# TestShem.net
KiCad netlist of a schematic drawn in EAGLE
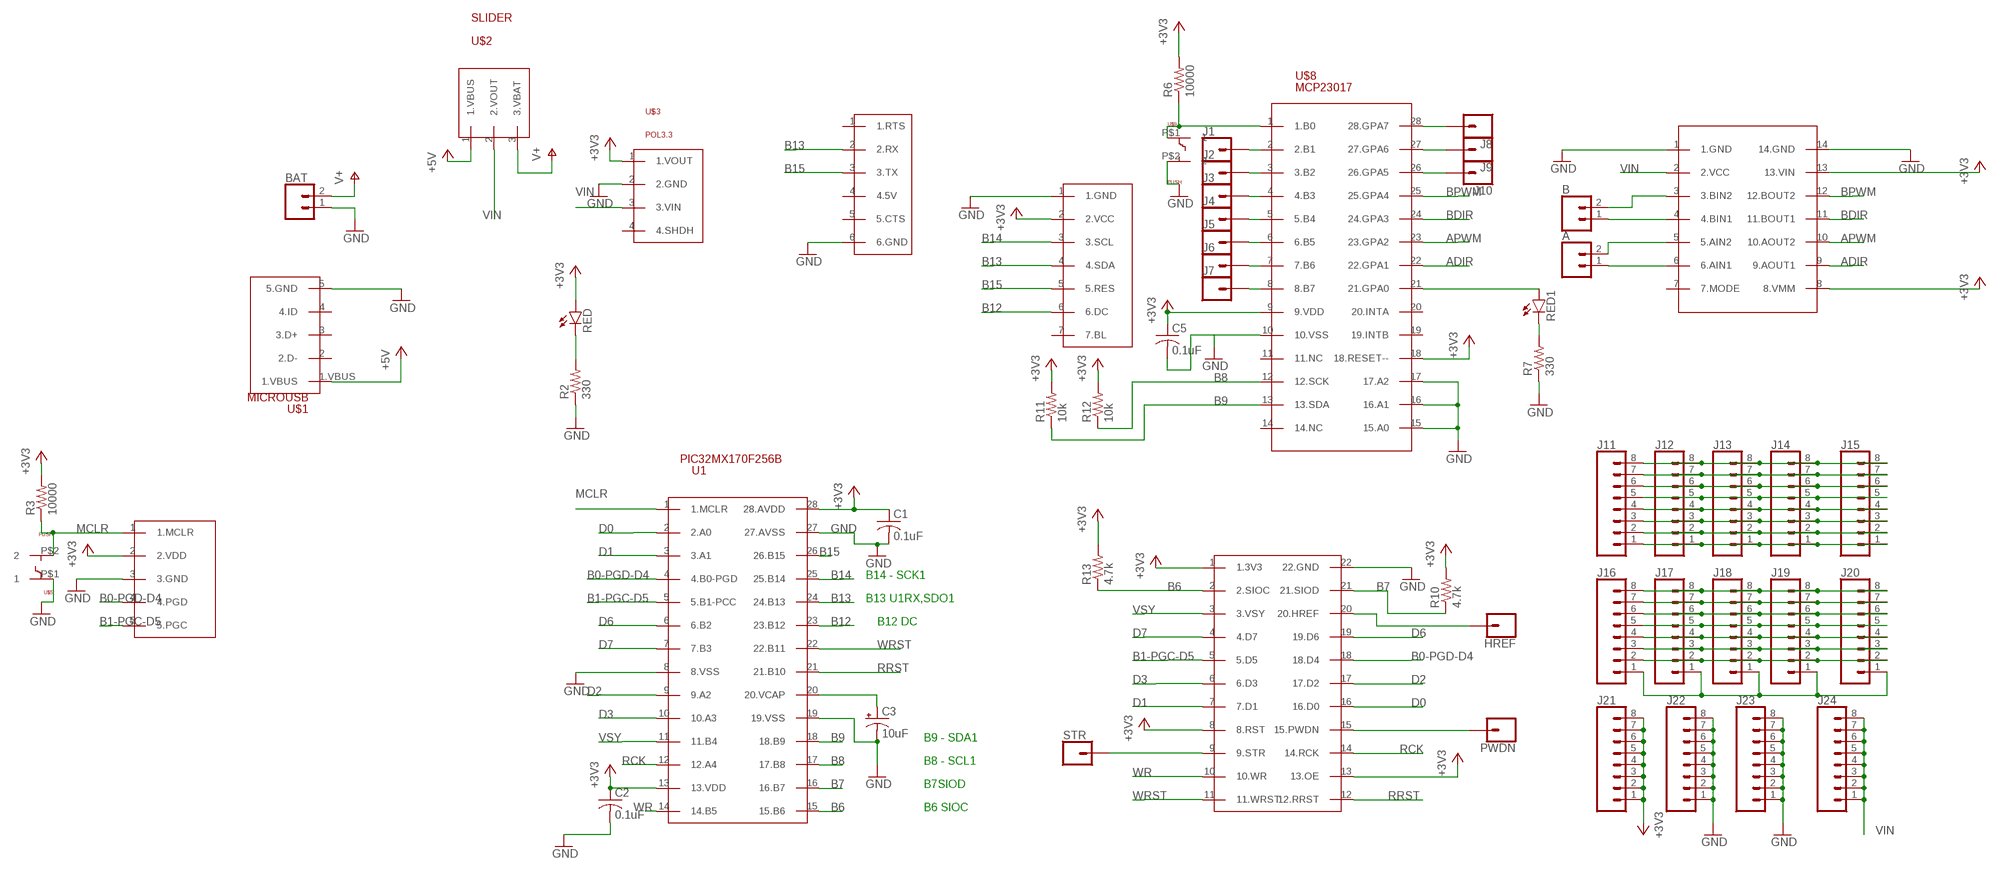
[diagram p0: schematic, sheet 1]

(export (version "E")
  (design (tool "Eeschema 10.0.6"))
  (components
    (comp (ref "A")
      (value "CONN_02")
      (footprint "eagle-import:1X02")
      (libsource (lib "eagle-import") (part "CONN_02"))
    )
    (comp (ref "B")
      (value "CONN_02")
      (footprint "eagle-import:1X02")
      (libsource (lib "eagle-import") (part "CONN_02"))
    )
    (comp (ref "BAT")
      (value "CONN_02")
      (footprint "eagle-import:1X02")
      (libsource (lib "eagle-import") (part "CONN_02"))
    )
    (comp (ref "C1")
      (value "0.1uF")
      (footprint "eagle-import:C025-030X050")
      (libsource (lib "eagle-import") (part "C-US025-030X050"))
    )
    (comp (ref "C2")
      (value "0.1uF")
      (footprint "eagle-import:C025-030X050")
      (libsource (lib "eagle-import") (part "C-US025-030X050"))
    )
    (comp (ref "C3")
      (value "10uF")
      (footprint "eagle-import:B45181B")
      (libsource (lib "eagle-import") (part "CPOL-USB45181B"))
    )
    (comp (ref "C5")
      (value "0.1uF")
      (footprint "eagle-import:C025-030X050")
      (libsource (lib "eagle-import") (part "C-US025-030X050"))
    )
    (comp (ref "HREF")
      (value "CONN_01")
      (footprint "eagle-import:1X01")
      (libsource (lib "eagle-import") (part "CONN_01"))
    )
    (comp (ref "J1")
      (value "CONN_01")
      (footprint "eagle-import:1X01")
      (libsource (lib "eagle-import") (part "CONN_01"))
    )
    (comp (ref "J2")
      (value "CONN_01")
      (footprint "eagle-import:1X01")
      (libsource (lib "eagle-import") (part "CONN_01"))
    )
    (comp (ref "J3")
      (value "CONN_01")
      (footprint "eagle-import:1X01")
      (libsource (lib "eagle-import") (part "CONN_01"))
    )
    (comp (ref "J4")
      (value "CONN_01")
      (footprint "eagle-import:1X01")
      (libsource (lib "eagle-import") (part "CONN_01"))
    )
    (comp (ref "J5")
      (value "CONN_01")
      (footprint "eagle-import:1X01")
      (libsource (lib "eagle-import") (part "CONN_01"))
    )
    (comp (ref "J6")
      (value "CONN_01")
      (footprint "eagle-import:1X01")
      (libsource (lib "eagle-import") (part "CONN_01"))
    )
    (comp (ref "J7")
      (value "CONN_01")
      (footprint "eagle-import:1X01")
      (libsource (lib "eagle-import") (part "CONN_01"))
    )
    (comp (ref "J8")
      (value "CONN_01")
      (footprint "eagle-import:1X01")
      (libsource (lib "eagle-import") (part "CONN_01"))
    )
    (comp (ref "J9")
      (value "CONN_01")
      (footprint "eagle-import:1X01")
      (libsource (lib "eagle-import") (part "CONN_01"))
    )
    (comp (ref "J10")
      (value "CONN_01")
      (footprint "eagle-import:1X01")
      (libsource (lib "eagle-import") (part "CONN_01"))
    )
    (comp (ref "J11")
      (value "CONN_08\"")
      (footprint "eagle-import:1X08")
      (libsource (lib "eagle-import") (part "CONN_08{dblquote}"))
    )
    (comp (ref "J12")
      (value "CONN_08\"")
      (footprint "eagle-import:1X08")
      (libsource (lib "eagle-import") (part "CONN_08{dblquote}"))
    )
    (comp (ref "J13")
      (value "CONN_08\"")
      (footprint "eagle-import:1X08")
      (libsource (lib "eagle-import") (part "CONN_08{dblquote}"))
    )
    (comp (ref "J14")
      (value "CONN_08\"")
      (footprint "eagle-import:1X08")
      (libsource (lib "eagle-import") (part "CONN_08{dblquote}"))
    )
    (comp (ref "J15")
      (value "CONN_08\"")
      (footprint "eagle-import:1X08")
      (libsource (lib "eagle-import") (part "CONN_08{dblquote}"))
    )
    (comp (ref "J16")
      (value "CONN_08\"")
      (footprint "eagle-import:1X08")
      (libsource (lib "eagle-import") (part "CONN_08{dblquote}"))
    )
    (comp (ref "J17")
      (value "CONN_08\"")
      (footprint "eagle-import:1X08")
      (libsource (lib "eagle-import") (part "CONN_08{dblquote}"))
    )
    (comp (ref "J18")
      (value "CONN_08\"")
      (footprint "eagle-import:1X08")
      (libsource (lib "eagle-import") (part "CONN_08{dblquote}"))
    )
    (comp (ref "J19")
      (value "CONN_08\"")
      (footprint "eagle-import:1X08")
      (libsource (lib "eagle-import") (part "CONN_08{dblquote}"))
    )
    (comp (ref "J20")
      (value "CONN_08\"")
      (footprint "eagle-import:1X08")
      (libsource (lib "eagle-import") (part "CONN_08{dblquote}"))
    )
    (comp (ref "J21")
      (value "CONN_08\"")
      (footprint "eagle-import:1X08")
      (libsource (lib "eagle-import") (part "CONN_08{dblquote}"))
    )
    (comp (ref "J22")
      (value "CONN_08\"")
      (footprint "eagle-import:1X08")
      (libsource (lib "eagle-import") (part "CONN_08{dblquote}"))
    )
    (comp (ref "J23")
      (value "CONN_08\"")
      (footprint "eagle-import:1X08")
      (libsource (lib "eagle-import") (part "CONN_08{dblquote}"))
    )
    (comp (ref "J24")
      (value "CONN_08\"")
      (footprint "eagle-import:1X08")
      (libsource (lib "eagle-import") (part "CONN_08{dblquote}"))
    )
    (comp (ref "PWDN")
      (value "CONN_01")
      (footprint "eagle-import:1X01")
      (libsource (lib "eagle-import") (part "CONN_01"))
    )
    (comp (ref "R2")
      (value "330")
      (footprint "eagle-import:0207_10")
      (libsource (lib "eagle-import") (part "R-US_0207/10"))
    )
    (comp (ref "R3")
      (value "10000")
      (footprint "eagle-import:0207_10")
      (libsource (lib "eagle-import") (part "R-US_0207/10"))
    )
    (comp (ref "R6")
      (value "10000")
      (footprint "eagle-import:0207_10")
      (libsource (lib "eagle-import") (part "R-US_0207/10"))
    )
    (comp (ref "R7")
      (value "330")
      (footprint "eagle-import:0207_10")
      (libsource (lib "eagle-import") (part "R-US_0207/10"))
    )
    (comp (ref "R10")
      (value "4.7k")
      (footprint "eagle-import:0207_10")
      (libsource (lib "eagle-import") (part "R-US_0207/10"))
    )
    (comp (ref "R11")
      (value "10k")
      (footprint "eagle-import:0207_10")
      (libsource (lib "eagle-import") (part "R-US_0207/10"))
    )
    (comp (ref "R12")
      (value "10k")
      (footprint "eagle-import:0207_10")
      (libsource (lib "eagle-import") (part "R-US_0207/10"))
    )
    (comp (ref "R13")
      (value "4.7k")
      (footprint "eagle-import:0207_10")
      (libsource (lib "eagle-import") (part "R-US_0207/10"))
    )
    (comp (ref "RED")
      (value "LED3MM")
      (footprint "eagle-import:LED3MM")
      (libsource (lib "eagle-import") (part "LED3MM"))
    )
    (comp (ref "RED1")
      (value "LED3MM")
      (footprint "eagle-import:LED3MM")
      (libsource (lib "eagle-import") (part "LED3MM"))
    )
    (comp (ref "STR")
      (value "CONN_01")
      (footprint "eagle-import:1X01")
      (libsource (lib "eagle-import") (part "CONN_01"))
    )
    (comp (ref "U$1")
      (value "MICROUSB")
      (footprint "eagle-import:MICROUSB")
      (libsource (lib "eagle-import") (part "MICROUSB"))
    )
    (comp (ref "U$2")
      (value "SLIDER")
      (footprint "eagle-import:SLIDER")
      (libsource (lib "eagle-import") (part "SLIDER"))
    )
    (comp (ref "U$3")
      (value "POL3.3")
      (footprint "eagle-import:POLOLU3.3")
      (libsource (lib "eagle-import") (part "POL3.3"))
    )
    (comp (ref "U$4")
      (value "SNAP")
      (footprint "eagle-import:1X05")
      (libsource (lib "eagle-import") (part "SNAP"))
    )
    (comp (ref "U$5")
      (value "PUSH")
      (footprint "eagle-import:PUSH")
      (libsource (lib "eagle-import") (part "PUSH"))
    )
    (comp (ref "U$6")
      (value "ADACP2104")
      (footprint "eagle-import:1X06V2")
      (libsource (lib "eagle-import") (part "ADACP2104"))
    )
    (comp (ref "U$7")
      (value "ST7789")
      (footprint "eagle-import:1X07")
      (libsource (lib "eagle-import") (part "ST7789"))
    )
    (comp (ref "U$8")
      (value "MCP23017")
      (footprint "eagle-import:DIL28-3")
      (libsource (lib "eagle-import") (part "MCP23017"))
    )
    (comp (ref "U$9")
      (value "PUSH")
      (footprint "eagle-import:PUSH")
      (libsource (lib "eagle-import") (part "PUSH"))
    )
    (comp (ref "U$10")
      (value "POLOLUDRV8835V2")
      (footprint "eagle-import:1X07V2")
      (libsource (lib "eagle-import") (part "POLOLUDRV8835V2"))
    )
    (comp (ref "U$11")
      (value "OV7670CAMFIXED")
      (footprint "eagle-import:1X02CAM")
      (libsource (lib "eagle-import") (part "OV7670CAMFIXED"))
    )
    (comp (ref "U1")
      (value "PIC32MX170F256B")
      (footprint "eagle-import:DIL28-3")
      (libsource (lib "eagle-import") (part "PIC32MX170F256B"))
    )
  )
  (nets
    (net (code "1") (name "+3V3") (class "Default")
      (node (ref "C1") (pin "1") (pinfunction "1_1") (pintype "passive"))
      (node (ref "C2") (pin "1") (pinfunction "1_1") (pintype "passive"))
      (node (ref "C5") (pin "1") (pinfunction "1_1") (pintype "passive"))
      (node (ref "J21") (pin "1") (pinfunction "1_1") (pintype "passive"))
      (node (ref "J21") (pin "2") (pinfunction "2_2") (pintype "passive"))
      (node (ref "J21") (pin "3") (pinfunction "3_3") (pintype "passive"))
      (node (ref "J21") (pin "4") (pinfunction "4_4") (pintype "passive"))
      (node (ref "J21") (pin "5") (pinfunction "5_5") (pintype "passive"))
      (node (ref "J21") (pin "6") (pinfunction "6_6") (pintype "passive"))
      (node (ref "J21") (pin "7") (pinfunction "7_7") (pintype "passive"))
      (node (ref "J21") (pin "8") (pinfunction "8_8") (pintype "passive"))
      (node (ref "R10") (pin "2") (pinfunction "2_2") (pintype "passive"))
      (node (ref "R11") (pin "2") (pinfunction "2_2") (pintype "passive"))
      (node (ref "R12") (pin "2") (pinfunction "2_2") (pintype "passive"))
      (node (ref "R13") (pin "2") (pinfunction "2_2") (pintype "passive"))
      (node (ref "R3") (pin "2") (pinfunction "2_2") (pintype "passive"))
      (node (ref "R6") (pin "2") (pinfunction "2_2") (pintype "passive"))
      (node (ref "RED") (pin "A") (pinfunction "A_A") (pintype "passive"))
      (node (ref "U$10") (pin "13") (pinfunction "13.VIN_13") (pintype "bidirectional"))
      (node (ref "U$10") (pin "8") (pinfunction "8.VMM_8") (pintype "bidirectional"))
      (node (ref "U$11") (pin "1") (pinfunction "1.3V3_1") (pintype "bidirectional"))
      (node (ref "U$11") (pin "13") (pinfunction "13.OE_13") (pintype "bidirectional"))
      (node (ref "U$11") (pin "8") (pinfunction "8.RST_8") (pintype "bidirectional"))
      (node (ref "U$3") (pin "1") (pinfunction "1.VOUT_1") (pintype "bidirectional"))
      (node (ref "U$4") (pin "2") (pinfunction "2.VDD_2") (pintype "bidirectional"))
      (node (ref "U$7") (pin "2") (pinfunction "2.VCC_2") (pintype "bidirectional"))
      (node (ref "U$8") (pin "18") (pinfunction "18.RESET--_18") (pintype "bidirectional"))
      (node (ref "U$8") (pin "9") (pinfunction "9.VDD_9") (pintype "bidirectional"))
      (node (ref "U1") (pin "13") (pinfunction "13.VDD_13") (pintype "bidirectional"))
      (node (ref "U1") (pin "28") (pinfunction "28.AVDD_28") (pintype "bidirectional"))
    )
    (net (code "2") (name "+5V") (class "Default")
      (node (ref "U$1") (pin "1.VBUS") (pinfunction "1.VBUS_1.VBUS") (pintype "bidirectional"))
      (node (ref "U$2") (pin "1") (pinfunction "1.VBUS_1") (pintype "bidirectional"))
    )
    (net (code "3") (name "/ADIR") (class "Default")
      (node (ref "U$10") (pin "9") (pinfunction "9.AOUT1_9") (pintype "bidirectional"))
      (node (ref "U$8") (pin "22") (pinfunction "22.GPA1_22") (pintype "bidirectional"))
    )
    (net (code "4") (name "/APWM") (class "Default")
      (node (ref "U$10") (pin "10") (pinfunction "10.AOUT2_10") (pintype "bidirectional"))
      (node (ref "U$8") (pin "23") (pinfunction "23.GPA2_23") (pintype "bidirectional"))
    )
    (net (code "5") (name "/B0-PGD-D4") (class "Default")
      (node (ref "U$11") (pin "18") (pinfunction "18.D4_18") (pintype "bidirectional"))
      (node (ref "U$4") (pin "4") (pinfunction "4.PGD_4") (pintype "bidirectional"))
      (node (ref "U1") (pin "4") (pinfunction "4.B0-PGD_4") (pintype "bidirectional"))
    )
    (net (code "6") (name "/B1-PGC-D5") (class "Default")
      (node (ref "U$11") (pin "5") (pinfunction "5.D5_5") (pintype "bidirectional"))
      (node (ref "U$4") (pin "5") (pinfunction "5.PGC_5") (pintype "bidirectional"))
      (node (ref "U1") (pin "5") (pinfunction "5.B1-PCC_5") (pintype "bidirectional"))
    )
    (net (code "7") (name "/B6") (class "Default")
      (node (ref "R13") (pin "1") (pinfunction "1_1") (pintype "passive"))
      (node (ref "U$11") (pin "2") (pinfunction "2.SIOC_2") (pintype "bidirectional"))
      (node (ref "U1") (pin "15") (pinfunction "15.B6_15") (pintype "bidirectional"))
    )
    (net (code "8") (name "/B7") (class "Default")
      (node (ref "R10") (pin "1") (pinfunction "1_1") (pintype "passive"))
      (node (ref "U$11") (pin "21") (pinfunction "21.SIOD_21") (pintype "bidirectional"))
      (node (ref "U1") (pin "16") (pinfunction "16.B7_16") (pintype "bidirectional"))
    )
    (net (code "9") (name "/B8") (class "Default")
      (node (ref "R12") (pin "1") (pinfunction "1_1") (pintype "passive"))
      (node (ref "U$8") (pin "12") (pinfunction "12.SCK_12") (pintype "bidirectional"))
      (node (ref "U1") (pin "17") (pinfunction "17.B8_17") (pintype "bidirectional"))
    )
    (net (code "10") (name "/B9") (class "Default")
      (node (ref "R11") (pin "1") (pinfunction "1_1") (pintype "passive"))
      (node (ref "U$8") (pin "13") (pinfunction "13.SDA_13") (pintype "bidirectional"))
      (node (ref "U1") (pin "18") (pinfunction "18.B9_18") (pintype "bidirectional"))
    )
    (net (code "11") (name "/B12") (class "Default")
      (node (ref "U$7") (pin "6") (pinfunction "6.DC_6") (pintype "bidirectional"))
      (node (ref "U1") (pin "23") (pinfunction "23.B12_23") (pintype "bidirectional"))
    )
    (net (code "12") (name "/B13") (class "Default")
      (node (ref "U$6") (pin "2") (pinfunction "2.RX_2") (pintype "bidirectional"))
      (node (ref "U$7") (pin "4") (pinfunction "4.SDA_4") (pintype "bidirectional"))
      (node (ref "U1") (pin "24") (pinfunction "24.B13_24") (pintype "bidirectional"))
    )
    (net (code "13") (name "/B14") (class "Default")
      (node (ref "U$7") (pin "3") (pinfunction "3.SCL_3") (pintype "bidirectional"))
      (node (ref "U1") (pin "25") (pinfunction "25.B14_25") (pintype "bidirectional"))
    )
    (net (code "14") (name "/B15") (class "Default")
      (node (ref "U$6") (pin "3") (pinfunction "3.TX_3") (pintype "bidirectional"))
      (node (ref "U$7") (pin "5") (pinfunction "5.RES_5") (pintype "bidirectional"))
      (node (ref "U1") (pin "26") (pinfunction "26.B15_26") (pintype "bidirectional"))
    )
    (net (code "15") (name "/BDIR") (class "Default")
      (node (ref "U$10") (pin "11") (pinfunction "11.BOUT1_11") (pintype "bidirectional"))
      (node (ref "U$8") (pin "24") (pinfunction "24.GPA3_24") (pintype "bidirectional"))
    )
    (net (code "16") (name "/BPWM") (class "Default")
      (node (ref "U$10") (pin "12") (pinfunction "12.BOUT2_12") (pintype "bidirectional"))
      (node (ref "U$8") (pin "25") (pinfunction "25.GPA4_25") (pintype "bidirectional"))
    )
    (net (code "17") (name "/D0") (class "Default")
      (node (ref "U$11") (pin "16") (pinfunction "16.D0_16") (pintype "bidirectional"))
      (node (ref "U1") (pin "2") (pinfunction "2.A0_2") (pintype "bidirectional"))
    )
    (net (code "18") (name "/D1") (class "Default")
      (node (ref "U$11") (pin "7") (pinfunction "7.D1_7") (pintype "bidirectional"))
      (node (ref "U1") (pin "3") (pinfunction "3.A1_3") (pintype "bidirectional"))
    )
    (net (code "19") (name "/D2") (class "Default")
      (node (ref "U$11") (pin "17") (pinfunction "17.D2_17") (pintype "bidirectional"))
      (node (ref "U1") (pin "9") (pinfunction "9.A2_9") (pintype "bidirectional"))
    )
    (net (code "20") (name "/D3") (class "Default")
      (node (ref "U$11") (pin "6") (pinfunction "6.D3_6") (pintype "bidirectional"))
      (node (ref "U1") (pin "10") (pinfunction "10.A3_10") (pintype "bidirectional"))
    )
    (net (code "21") (name "/D6") (class "Default")
      (node (ref "U$11") (pin "19") (pinfunction "19.D6_19") (pintype "bidirectional"))
      (node (ref "U1") (pin "6") (pinfunction "6.B2_6") (pintype "bidirectional"))
    )
    (net (code "22") (name "/D7") (class "Default")
      (node (ref "U$11") (pin "4") (pinfunction "4.D7_4") (pintype "bidirectional"))
      (node (ref "U1") (pin "7") (pinfunction "7.B3_7") (pintype "bidirectional"))
    )
    (net (code "23") (name "/MCLR") (class "Default")
      (node (ref "R3") (pin "1") (pinfunction "1_1") (pintype "passive"))
      (node (ref "U$4") (pin "1") (pinfunction "1.MCLR_1") (pintype "bidirectional"))
      (node (ref "U$5") (pin "P$2") (pinfunction "2_P$2") (pintype "bidirectional"))
      (node (ref "U1") (pin "1") (pinfunction "1.MCLR_1") (pintype "bidirectional"))
    )
    (net (code "24") (name "/RCK") (class "Default")
      (node (ref "U$11") (pin "14") (pinfunction "14.RCK_14") (pintype "bidirectional"))
      (node (ref "U1") (pin "12") (pinfunction "12.A4_12") (pintype "bidirectional"))
    )
    (net (code "25") (name "/RRST") (class "Default")
      (node (ref "U$11") (pin "12") (pinfunction "12.RRST_12") (pintype "bidirectional"))
      (node (ref "U1") (pin "21") (pinfunction "21.B10_21") (pintype "bidirectional"))
    )
    (net (code "26") (name "/VIN") (class "Default")
      (node (ref "J24") (pin "1") (pinfunction "1_1") (pintype "passive"))
      (node (ref "J24") (pin "2") (pinfunction "2_2") (pintype "passive"))
      (node (ref "J24") (pin "3") (pinfunction "3_3") (pintype "passive"))
      (node (ref "J24") (pin "4") (pinfunction "4_4") (pintype "passive"))
      (node (ref "J24") (pin "5") (pinfunction "5_5") (pintype "passive"))
      (node (ref "J24") (pin "6") (pinfunction "6_6") (pintype "passive"))
      (node (ref "J24") (pin "7") (pinfunction "7_7") (pintype "passive"))
      (node (ref "J24") (pin "8") (pinfunction "8_8") (pintype "passive"))
      (node (ref "U$10") (pin "2") (pinfunction "2.VCC_2") (pintype "bidirectional"))
      (node (ref "U$2") (pin "2") (pinfunction "2.VOUT_2") (pintype "bidirectional"))
      (node (ref "U$3") (pin "3") (pinfunction "3.VIN_3") (pintype "bidirectional"))
    )
    (net (code "27") (name "/VSY") (class "Default")
      (node (ref "U$11") (pin "3") (pinfunction "3.VSY_3") (pintype "bidirectional"))
      (node (ref "U1") (pin "11") (pinfunction "11.B4_11") (pintype "bidirectional"))
    )
    (net (code "28") (name "/WR") (class "Default")
      (node (ref "U$11") (pin "10") (pinfunction "10.WR_10") (pintype "bidirectional"))
      (node (ref "U1") (pin "14") (pinfunction "14.B5_14") (pintype "bidirectional"))
    )
    (net (code "29") (name "/WRST") (class "Default")
      (node (ref "U$11") (pin "11") (pinfunction "11.WRST_11") (pintype "bidirectional"))
      (node (ref "U1") (pin "22") (pinfunction "22.B11_22") (pintype "bidirectional"))
    )
    (net (code "30") (name "GND") (class "Default")
      (node (ref "BAT") (pin "1") (pinfunction "1_1") (pintype "passive"))
      (node (ref "C1") (pin "2") (pinfunction "2_2") (pintype "passive"))
      (node (ref "C2") (pin "2") (pinfunction "2_2") (pintype "passive"))
      (node (ref "C3") (pin "-") (pinfunction "-_-") (pintype "passive"))
      (node (ref "J22") (pin "1") (pinfunction "1_1") (pintype "passive"))
      (node (ref "J22") (pin "2") (pinfunction "2_2") (pintype "passive"))
      (node (ref "J22") (pin "3") (pinfunction "3_3") (pintype "passive"))
      (node (ref "J22") (pin "4") (pinfunction "4_4") (pintype "passive"))
      (node (ref "J22") (pin "5") (pinfunction "5_5") (pintype "passive"))
      (node (ref "J22") (pin "6") (pinfunction "6_6") (pintype "passive"))
      (node (ref "J22") (pin "7") (pinfunction "7_7") (pintype "passive"))
      (node (ref "J22") (pin "8") (pinfunction "8_8") (pintype "passive"))
      (node (ref "J23") (pin "1") (pinfunction "1_1") (pintype "passive"))
      (node (ref "J23") (pin "2") (pinfunction "2_2") (pintype "passive"))
      (node (ref "J23") (pin "3") (pinfunction "3_3") (pintype "passive"))
      (node (ref "J23") (pin "4") (pinfunction "4_4") (pintype "passive"))
      (node (ref "J23") (pin "5") (pinfunction "5_5") (pintype "passive"))
      (node (ref "J23") (pin "6") (pinfunction "6_6") (pintype "passive"))
      (node (ref "J23") (pin "7") (pinfunction "7_7") (pintype "passive"))
      (node (ref "J23") (pin "8") (pinfunction "8_8") (pintype "passive"))
      (node (ref "R2") (pin "1") (pinfunction "1_1") (pintype "passive"))
      (node (ref "R7") (pin "1") (pinfunction "1_1") (pintype "passive"))
      (node (ref "U$1") (pin "5") (pinfunction "5.GND_5") (pintype "bidirectional"))
      (node (ref "U$10") (pin "1") (pinfunction "1.GND_1") (pintype "bidirectional"))
      (node (ref "U$10") (pin "14") (pinfunction "14.GND_14") (pintype "bidirectional"))
      (node (ref "U$11") (pin "22") (pinfunction "22.GND_22") (pintype "bidirectional"))
      (node (ref "U$3") (pin "2") (pinfunction "2.GND_2") (pintype "bidirectional"))
      (node (ref "U$4") (pin "3") (pinfunction "3.GND_3") (pintype "bidirectional"))
      (node (ref "U$5") (pin "P$1") (pinfunction "1_P$1") (pintype "bidirectional"))
      (node (ref "U$6") (pin "6") (pinfunction "6.GND_6") (pintype "bidirectional"))
      (node (ref "U$7") (pin "1") (pinfunction "1.GND_1") (pintype "bidirectional"))
      (node (ref "U$8") (pin "15") (pinfunction "15.A0_15") (pintype "bidirectional"))
      (node (ref "U$8") (pin "16") (pinfunction "16.A1_16") (pintype "bidirectional"))
      (node (ref "U$8") (pin "17") (pinfunction "17.A2_17") (pintype "bidirectional"))
      (node (ref "U$9") (pin "P$2") (pinfunction "2_P$2") (pintype "bidirectional"))
      (node (ref "U1") (pin "19") (pinfunction "19.VSS_19") (pintype "bidirectional"))
      (node (ref "U1") (pin "27") (pinfunction "27.AVSS_27") (pintype "bidirectional"))
      (node (ref "U1") (pin "8") (pinfunction "8.VSS_8") (pintype "bidirectional"))
    )
    (net (code "31") (name "Net-(J11-Pad1)") (class "Default")
      (node (ref "J11") (pin "1") (pinfunction "1_1") (pintype "passive"))
      (node (ref "J12") (pin "1") (pinfunction "1_1") (pintype "passive"))
      (node (ref "J13") (pin "1") (pinfunction "1_1") (pintype "passive"))
      (node (ref "J14") (pin "1") (pinfunction "1_1") (pintype "passive"))
      (node (ref "J15") (pin "1") (pinfunction "1_1") (pintype "passive"))
    )
    (net (code "32") (name "Net-(J11-Pad2)") (class "Default")
      (node (ref "J11") (pin "2") (pinfunction "2_2") (pintype "passive"))
      (node (ref "J12") (pin "2") (pinfunction "2_2") (pintype "passive"))
      (node (ref "J13") (pin "2") (pinfunction "2_2") (pintype "passive"))
      (node (ref "J14") (pin "2") (pinfunction "2_2") (pintype "passive"))
      (node (ref "J15") (pin "2") (pinfunction "2_2") (pintype "passive"))
    )
    (net (code "33") (name "Net-(J11-Pad3)") (class "Default")
      (node (ref "J11") (pin "3") (pinfunction "3_3") (pintype "passive"))
      (node (ref "J12") (pin "3") (pinfunction "3_3") (pintype "passive"))
      (node (ref "J13") (pin "3") (pinfunction "3_3") (pintype "passive"))
      (node (ref "J14") (pin "3") (pinfunction "3_3") (pintype "passive"))
      (node (ref "J15") (pin "3") (pinfunction "3_3") (pintype "passive"))
    )
    (net (code "34") (name "Net-(J11-Pad4)") (class "Default")
      (node (ref "J11") (pin "4") (pinfunction "4_4") (pintype "passive"))
      (node (ref "J12") (pin "4") (pinfunction "4_4") (pintype "passive"))
      (node (ref "J13") (pin "4") (pinfunction "4_4") (pintype "passive"))
      (node (ref "J14") (pin "4") (pinfunction "4_4") (pintype "passive"))
      (node (ref "J15") (pin "4") (pinfunction "4_4") (pintype "passive"))
    )
    (net (code "35") (name "Net-(J11-Pad5)") (class "Default")
      (node (ref "J11") (pin "5") (pinfunction "5_5") (pintype "passive"))
      (node (ref "J12") (pin "5") (pinfunction "5_5") (pintype "passive"))
      (node (ref "J13") (pin "5") (pinfunction "5_5") (pintype "passive"))
      (node (ref "J14") (pin "5") (pinfunction "5_5") (pintype "passive"))
      (node (ref "J15") (pin "5") (pinfunction "5_5") (pintype "passive"))
    )
    (net (code "36") (name "Net-(J11-Pad6)") (class "Default")
      (node (ref "J11") (pin "6") (pinfunction "6_6") (pintype "passive"))
      (node (ref "J12") (pin "6") (pinfunction "6_6") (pintype "passive"))
      (node (ref "J13") (pin "6") (pinfunction "6_6") (pintype "passive"))
      (node (ref "J14") (pin "6") (pinfunction "6_6") (pintype "passive"))
      (node (ref "J15") (pin "6") (pinfunction "6_6") (pintype "passive"))
    )
    (net (code "37") (name "Net-(J11-Pad7)") (class "Default")
      (node (ref "J11") (pin "7") (pinfunction "7_7") (pintype "passive"))
      (node (ref "J12") (pin "7") (pinfunction "7_7") (pintype "passive"))
      (node (ref "J13") (pin "7") (pinfunction "7_7") (pintype "passive"))
      (node (ref "J14") (pin "7") (pinfunction "7_7") (pintype "passive"))
      (node (ref "J15") (pin "7") (pinfunction "7_7") (pintype "passive"))
    )
    (net (code "38") (name "Net-(J11-Pad8)") (class "Default")
      (node (ref "J11") (pin "8") (pinfunction "8_8") (pintype "passive"))
      (node (ref "J12") (pin "8") (pinfunction "8_8") (pintype "passive"))
      (node (ref "J13") (pin "8") (pinfunction "8_8") (pintype "passive"))
      (node (ref "J14") (pin "8") (pinfunction "8_8") (pintype "passive"))
      (node (ref "J15") (pin "8") (pinfunction "8_8") (pintype "passive"))
    )
    (net (code "39") (name "Net-(J16-Pad1)") (class "Default")
      (node (ref "J16") (pin "1") (pinfunction "1_1") (pintype "passive"))
      (node (ref "J17") (pin "1") (pinfunction "1_1") (pintype "passive"))
      (node (ref "J18") (pin "1") (pinfunction "1_1") (pintype "passive"))
      (node (ref "J19") (pin "1") (pinfunction "1_1") (pintype "passive"))
      (node (ref "J20") (pin "1") (pinfunction "1_1") (pintype "passive"))
    )
    (net (code "40") (name "Net-(J16-Pad2)") (class "Default")
      (node (ref "J16") (pin "2") (pinfunction "2_2") (pintype "passive"))
      (node (ref "J17") (pin "2") (pinfunction "2_2") (pintype "passive"))
      (node (ref "J18") (pin "2") (pinfunction "2_2") (pintype "passive"))
      (node (ref "J19") (pin "2") (pinfunction "2_2") (pintype "passive"))
      (node (ref "J20") (pin "2") (pinfunction "2_2") (pintype "passive"))
    )
    (net (code "41") (name "Net-(J16-Pad3)") (class "Default")
      (node (ref "J16") (pin "3") (pinfunction "3_3") (pintype "passive"))
      (node (ref "J17") (pin "3") (pinfunction "3_3") (pintype "passive"))
      (node (ref "J18") (pin "3") (pinfunction "3_3") (pintype "passive"))
      (node (ref "J19") (pin "3") (pinfunction "3_3") (pintype "passive"))
      (node (ref "J20") (pin "3") (pinfunction "3_3") (pintype "passive"))
    )
    (net (code "42") (name "Net-(J16-Pad4)") (class "Default")
      (node (ref "J16") (pin "4") (pinfunction "4_4") (pintype "passive"))
      (node (ref "J17") (pin "4") (pinfunction "4_4") (pintype "passive"))
      (node (ref "J18") (pin "4") (pinfunction "4_4") (pintype "passive"))
      (node (ref "J19") (pin "4") (pinfunction "4_4") (pintype "passive"))
      (node (ref "J20") (pin "4") (pinfunction "4_4") (pintype "passive"))
    )
    (net (code "43") (name "Net-(J16-Pad5)") (class "Default")
      (node (ref "J16") (pin "5") (pinfunction "5_5") (pintype "passive"))
      (node (ref "J17") (pin "5") (pinfunction "5_5") (pintype "passive"))
      (node (ref "J18") (pin "5") (pinfunction "5_5") (pintype "passive"))
      (node (ref "J19") (pin "5") (pinfunction "5_5") (pintype "passive"))
      (node (ref "J20") (pin "5") (pinfunction "5_5") (pintype "passive"))
    )
    (net (code "44") (name "Net-(J16-Pad6)") (class "Default")
      (node (ref "J16") (pin "6") (pinfunction "6_6") (pintype "passive"))
      (node (ref "J17") (pin "6") (pinfunction "6_6") (pintype "passive"))
      (node (ref "J18") (pin "6") (pinfunction "6_6") (pintype "passive"))
      (node (ref "J19") (pin "6") (pinfunction "6_6") (pintype "passive"))
      (node (ref "J20") (pin "6") (pinfunction "6_6") (pintype "passive"))
    )
    (net (code "45") (name "Net-(J16-Pad7)") (class "Default")
      (node (ref "J16") (pin "7") (pinfunction "7_7") (pintype "passive"))
      (node (ref "J17") (pin "7") (pinfunction "7_7") (pintype "passive"))
      (node (ref "J18") (pin "7") (pinfunction "7_7") (pintype "passive"))
      (node (ref "J19") (pin "7") (pinfunction "7_7") (pintype "passive"))
      (node (ref "J20") (pin "7") (pinfunction "7_7") (pintype "passive"))
    )
    (net (code "46") (name "Net-(J16-Pad8)") (class "Default")
      (node (ref "J16") (pin "8") (pinfunction "8_8") (pintype "passive"))
      (node (ref "J17") (pin "8") (pinfunction "8_8") (pintype "passive"))
      (node (ref "J18") (pin "8") (pinfunction "8_8") (pintype "passive"))
      (node (ref "J19") (pin "8") (pinfunction "8_8") (pintype "passive"))
      (node (ref "J20") (pin "8") (pinfunction "8_8") (pintype "passive"))
    )
    (net (code "47") (name "Net-(RED-C)") (class "Default")
      (node (ref "R2") (pin "2") (pinfunction "2_2") (pintype "passive"))
      (node (ref "RED") (pin "K") (pinfunction "C_K") (pintype "passive"))
    )
    (net (code "48") (name "Net-(RED1-C)") (class "Default")
      (node (ref "R7") (pin "2") (pinfunction "2_2") (pintype "passive"))
      (node (ref "RED1") (pin "K") (pinfunction "C_K") (pintype "passive"))
    )
    (net (code "49") (name "Net-(U$8-1.B0)") (class "Default")
      (node (ref "R6") (pin "1") (pinfunction "1_1") (pintype "passive"))
      (node (ref "U$8") (pin "1") (pinfunction "1.B0_1") (pintype "bidirectional"))
      (node (ref "U$9") (pin "P$1") (pinfunction "1_P$1") (pintype "bidirectional"))
    )
    (net (code "50") (name "Net-(U$8-2.B1)") (class "Default")
      (node (ref "J1") (pin "1") (pinfunction "1_1") (pintype "passive"))
      (node (ref "U$8") (pin "2") (pinfunction "2.B1_2") (pintype "bidirectional"))
    )
    (net (code "51") (name "Net-(U$8-3.B2)") (class "Default")
      (node (ref "J2") (pin "1") (pinfunction "1_1") (pintype "passive"))
      (node (ref "U$8") (pin "3") (pinfunction "3.B2_3") (pintype "bidirectional"))
    )
    (net (code "52") (name "Net-(U$8-4.B3)") (class "Default")
      (node (ref "J3") (pin "1") (pinfunction "1_1") (pintype "passive"))
      (node (ref "U$8") (pin "4") (pinfunction "4.B3_4") (pintype "bidirectional"))
    )
    (net (code "53") (name "Net-(U$8-5.B4)") (class "Default")
      (node (ref "J4") (pin "1") (pinfunction "1_1") (pintype "passive"))
      (node (ref "U$8") (pin "5") (pinfunction "5.B4_5") (pintype "bidirectional"))
    )
    (net (code "54") (name "Net-(U$8-6.B5)") (class "Default")
      (node (ref "J5") (pin "1") (pinfunction "1_1") (pintype "passive"))
      (node (ref "U$8") (pin "6") (pinfunction "6.B5_6") (pintype "bidirectional"))
    )
    (net (code "55") (name "Net-(U$8-7.B6)") (class "Default")
      (node (ref "J6") (pin "1") (pinfunction "1_1") (pintype "passive"))
      (node (ref "U$8") (pin "7") (pinfunction "7.B6_7") (pintype "bidirectional"))
    )
    (net (code "56") (name "Net-(U$8-8.B7)") (class "Default")
      (node (ref "J7") (pin "1") (pinfunction "1_1") (pintype "passive"))
      (node (ref "U$8") (pin "8") (pinfunction "8.B7_8") (pintype "bidirectional"))
    )
    (net (code "57") (name "Net-(U$8-10.VSS)") (class "Default")
      (node (ref "C5") (pin "2") (pinfunction "2_2") (pintype "passive"))
      (node (ref "U$8") (pin "10") (pinfunction "10.VSS_10") (pintype "bidirectional"))
    )
    (net (code "58") (name "Net-(U$8-21.GPA0)") (class "Default")
      (node (ref "RED1") (pin "A") (pinfunction "A_A") (pintype "passive"))
      (node (ref "U$8") (pin "21") (pinfunction "21.GPA0_21") (pintype "bidirectional"))
    )
    (net (code "59") (name "Net-(U$8-26.GPA5)") (class "Default")
      (node (ref "J10") (pin "1") (pinfunction "1_1") (pintype "passive"))
      (node (ref "U$8") (pin "26") (pinfunction "26.GPA5_26") (pintype "bidirectional"))
    )
    (net (code "60") (name "Net-(U$8-27.GPA6)") (class "Default")
      (node (ref "J9") (pin "1") (pinfunction "1_1") (pintype "passive"))
      (node (ref "U$8") (pin "27") (pinfunction "27.GPA6_27") (pintype "bidirectional"))
    )
    (net (code "61") (name "Net-(U$8-28.GPA7)") (class "Default")
      (node (ref "J8") (pin "1") (pinfunction "1_1") (pintype "passive"))
      (node (ref "U$8") (pin "28") (pinfunction "28.GPA7_28") (pintype "bidirectional"))
    )
    (net (code "62") (name "Net-(U$10-3.BIN2)") (class "Default")
      (node (ref "B") (pin "2") (pinfunction "2_2") (pintype "passive"))
      (node (ref "U$10") (pin "3") (pinfunction "3.BIN2_3") (pintype "bidirectional"))
    )
    (net (code "63") (name "Net-(U$10-4.BIN1)") (class "Default")
      (node (ref "B") (pin "1") (pinfunction "1_1") (pintype "passive"))
      (node (ref "U$10") (pin "4") (pinfunction "4.BIN1_4") (pintype "bidirectional"))
    )
    (net (code "64") (name "Net-(U$10-5.AIN2)") (class "Default")
      (node (ref "A") (pin "2") (pinfunction "2_2") (pintype "passive"))
      (node (ref "U$10") (pin "5") (pinfunction "5.AIN2_5") (pintype "bidirectional"))
    )
    (net (code "65") (name "Net-(U$10-6.AIN1)") (class "Default")
      (node (ref "A") (pin "1") (pinfunction "1_1") (pintype "passive"))
      (node (ref "U$10") (pin "6") (pinfunction "6.AIN1_6") (pintype "bidirectional"))
    )
    (net (code "66") (name "Net-(U$11-9.STR)") (class "Default")
      (node (ref "STR") (pin "1") (pinfunction "1_1") (pintype "passive"))
      (node (ref "U$11") (pin "9") (pinfunction "9.STR_9") (pintype "bidirectional"))
    )
    (net (code "67") (name "Net-(U$11-15.PWDN)") (class "Default")
      (node (ref "PWDN") (pin "1") (pinfunction "1_1") (pintype "passive"))
      (node (ref "U$11") (pin "15") (pinfunction "15.PWDN_15") (pintype "bidirectional"))
    )
    (net (code "68") (name "Net-(U$11-20.HREF)") (class "Default")
      (node (ref "HREF") (pin "1") (pinfunction "1_1") (pintype "passive"))
      (node (ref "U$11") (pin "20") (pinfunction "20.HREF_20") (pintype "bidirectional"))
    )
    (net (code "69") (name "Net-(U1-20.VCAP)") (class "Default")
      (node (ref "C3") (pin "+") (pinfunction "+_+") (pintype "passive"))
      (node (ref "U1") (pin "20") (pinfunction "20.VCAP_20") (pintype "bidirectional"))
    )
    (net (code "70") (name "V+") (class "Default")
      (node (ref "BAT") (pin "2") (pinfunction "2_2") (pintype "passive"))
      (node (ref "U$2") (pin "3") (pinfunction "3.VBAT_3") (pintype "bidirectional"))
    )
    (net (code "71") (name "unconnected-(U$1-2.D--Pad2)") (class "Default")
      (node (ref "U$1") (pin "2") (pinfunction "2.D-_2") (pintype "bidirectional"))
    )
    (net (code "72") (name "unconnected-(U$1-3.D+-Pad3)") (class "Default")
      (node (ref "U$1") (pin "3") (pinfunction "3.D+_3") (pintype "bidirectional"))
    )
    (net (code "73") (name "unconnected-(U$1-4.ID-Pad4)") (class "Default")
      (node (ref "U$1") (pin "4") (pinfunction "4.ID_4") (pintype "bidirectional"))
    )
    (net (code "74") (name "unconnected-(U$3-4.SHDH-Pad4)") (class "Default")
      (node (ref "U$3") (pin "4") (pinfunction "4.SHDH_4") (pintype "bidirectional"))
    )
    (net (code "75") (name "unconnected-(U$6-1.RTS-Pad1)") (class "Default")
      (node (ref "U$6") (pin "1") (pinfunction "1.RTS_1") (pintype "bidirectional"))
    )
    (net (code "76") (name "unconnected-(U$6-4.5V-Pad4)") (class "Default")
      (node (ref "U$6") (pin "4") (pinfunction "4.5V_4") (pintype "bidirectional"))
    )
    (net (code "77") (name "unconnected-(U$6-5.CTS-Pad5)") (class "Default")
      (node (ref "U$6") (pin "5") (pinfunction "5.CTS_5") (pintype "bidirectional"))
    )
    (net (code "78") (name "unconnected-(U$7-7.BL-Pad7)") (class "Default")
      (node (ref "U$7") (pin "7") (pinfunction "7.BL_7") (pintype "bidirectional"))
    )
    (net (code "79") (name "unconnected-(U$8-11.NC-Pad11)") (class "Default")
      (node (ref "U$8") (pin "11") (pinfunction "11.NC_11") (pintype "bidirectional"))
    )
    (net (code "80") (name "unconnected-(U$8-14.NC-Pad14)") (class "Default")
      (node (ref "U$8") (pin "14") (pinfunction "14.NC_14") (pintype "bidirectional"))
    )
    (net (code "81") (name "unconnected-(U$8-19.INTB-Pad19)") (class "Default")
      (node (ref "U$8") (pin "19") (pinfunction "19.INTB_19") (pintype "bidirectional"))
    )
    (net (code "82") (name "unconnected-(U$8-20.INTA-Pad20)") (class "Default")
      (node (ref "U$8") (pin "20") (pinfunction "20.INTA_20") (pintype "bidirectional"))
    )
    (net (code "83") (name "unconnected-(U$10-7.MODE-Pad7)") (class "Default")
      (node (ref "U$10") (pin "7") (pinfunction "7.MODE_7") (pintype "bidirectional"))
    )
  )
)
